# Sheet1.net
KiCad netlist of a schematic drawn in Altium Designer
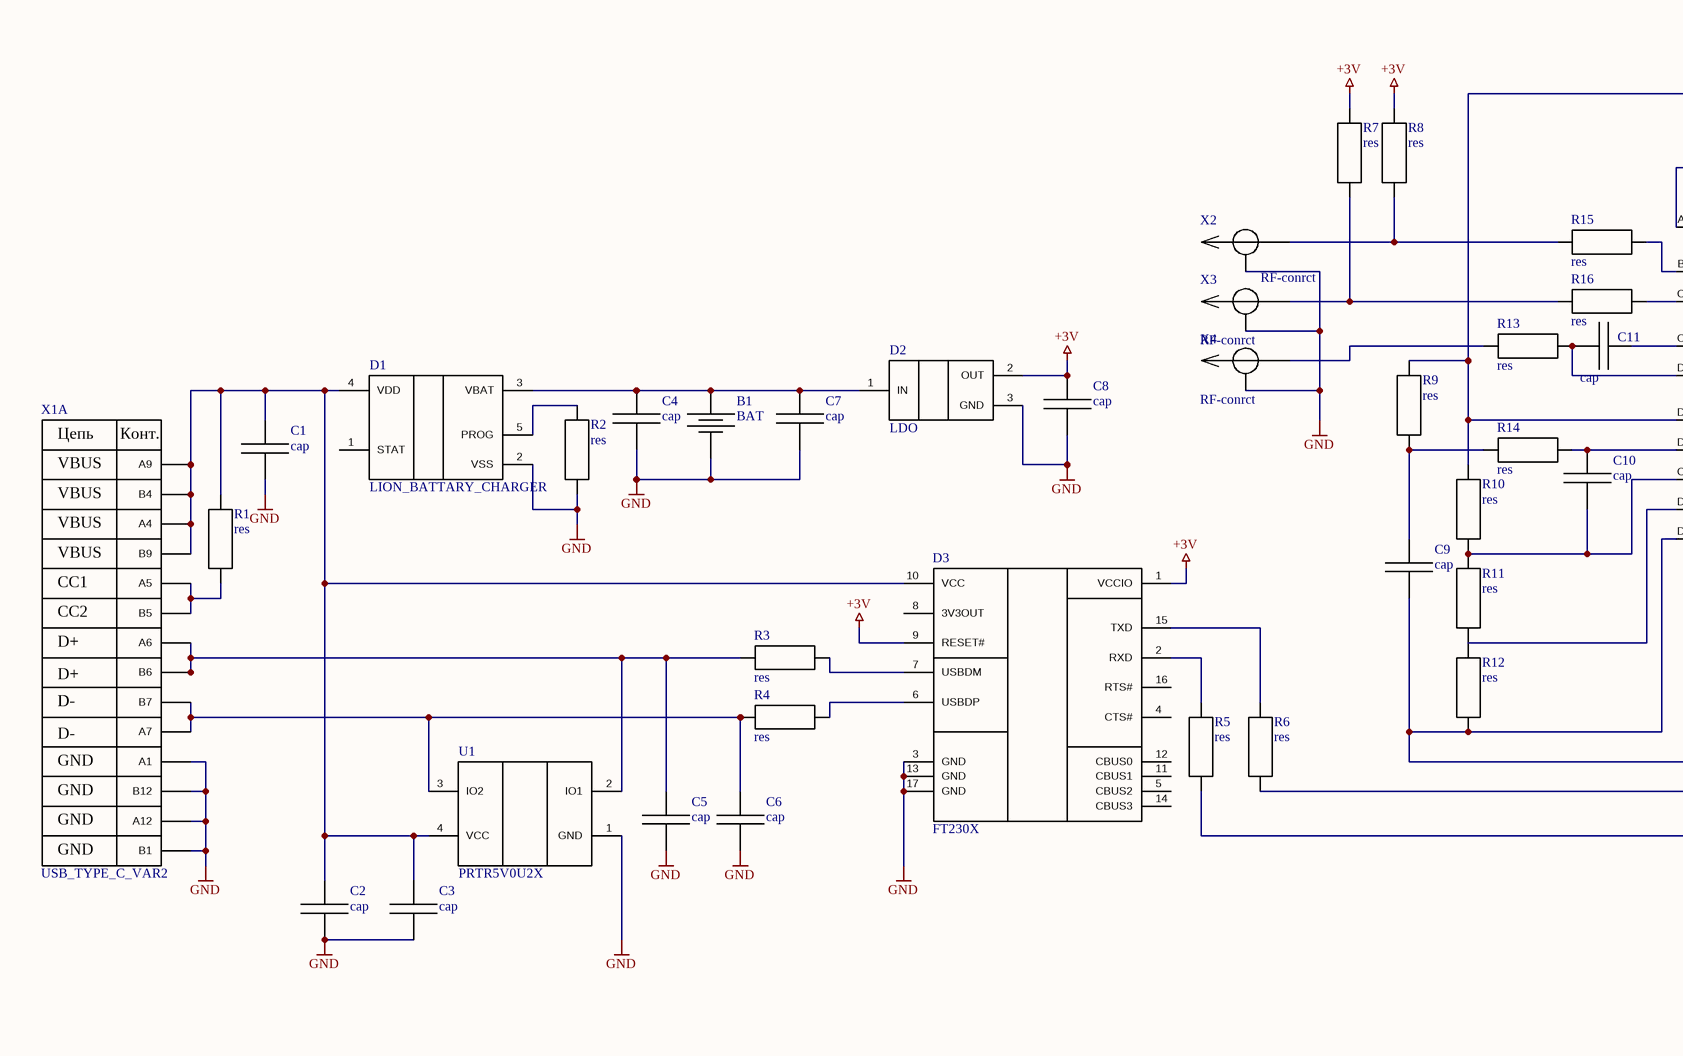
[diagram p0: Sheet1.SchDoc, left]
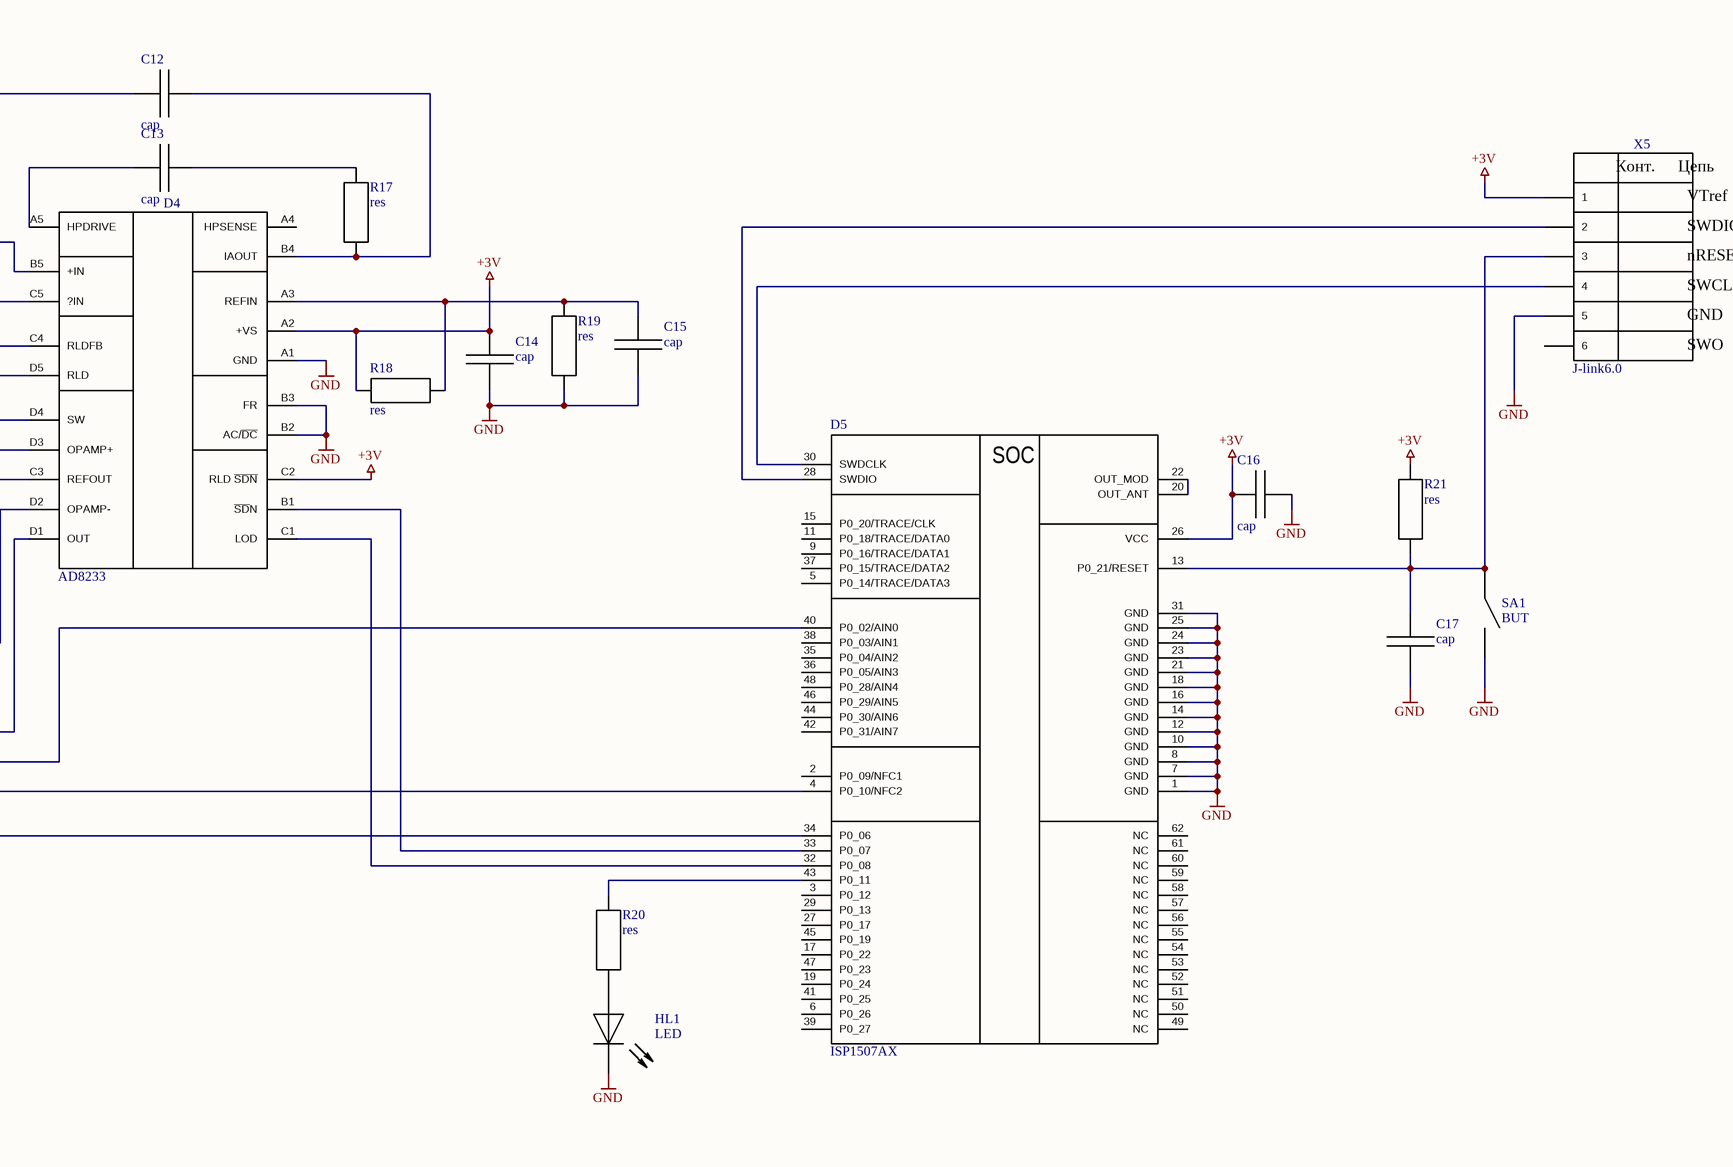
[diagram p1: Sheet1.SchDoc, right]

(export (version "E")
  (design (tool "Eeschema 10.0.6"))
  (components
    (comp (ref "B1")
      (value "BAT")
      (footprint "lION")
      (fields
        (field (name "PART NUMBER") "Li-Polymer 402025")
        (field (name "VOLTAGE") "3.7")
        (field (name "MANUFACTURER") "PKCELL")
      )
      (libsource (lib "lib_for_test_work") (part "BAT"))
    )
    (comp (ref "C1")
      (value "cap")
      (footprint "CAP0805")
      (fields
        (field (name "PART NUMBER") "GRM21BR71C475KA73L")
        (field (name "VOLTAGE") "16V")
        (field (name "MANUFACTURER") "Murata")
      )
      (libsource (lib "lib_for_test_work") (part "cap"))
    )
    (comp (ref "C2")
      (value "cap")
      (footprint "CAP0805")
      (fields
        (field (name "PART NUMBER") "GRM21BR71C475KA73L")
        (field (name "VOLTAGE") "16V")
        (field (name "MANUFACTURER") "Murata")
      )
      (libsource (lib "lib_for_test_work") (part "cap"))
    )
    (comp (ref "C3")
      (value "cap")
      (footprint "CAP0402")
      (fields
        (field (name "PART NUMBER") "GRM155R71C104K")
        (field (name "VOLTAGE") "10V")
        (field (name "MANUFACTURER") "Murata")
      )
      (libsource (lib "lib_for_test_work") (part "cap"))
    )
    (comp (ref "C4")
      (value "cap")
      (footprint "CAP0805")
      (fields
        (field (name "PART NUMBER") "GRM21BR71C475KA73L")
        (field (name "VOLTAGE") "16V")
        (field (name "MANUFACTURER") "Murata")
      )
      (libsource (lib "lib_for_test_work") (part "cap"))
    )
    (comp (ref "C5")
      (value "cap")
      (footprint "CAP0402")
      (fields
        (field (name "PART NUMBER") "GRM1555C1H470J")
        (field (name "VOLTAGE") "16V")
        (field (name "MANUFACTURER") "Murata")
      )
      (libsource (lib "lib_for_test_work") (part "cap"))
    )
    (comp (ref "C6")
      (value "cap")
      (footprint "CAP0402")
      (fields
        (field (name "PART NUMBER") "GRM1555C1H470J")
        (field (name "VOLTAGE") "16V")
        (field (name "MANUFACTURER") "Murata")
      )
      (libsource (lib "lib_for_test_work") (part "cap"))
    )
    (comp (ref "C7")
      (value "cap")
      (footprint "CAP0402")
      (fields
        (field (name "PART NUMBER") "GRM155R71C104K")
        (field (name "VOLTAGE") "10V")
        (field (name "MANUFACTURER") "Murata")
      )
      (libsource (lib "lib_for_test_work") (part "cap"))
    )
    (comp (ref "C8")
      (value "cap")
      (footprint "CAP0402")
      (fields
        (field (name "PART NUMBER") "GRM155R71C104K")
        (field (name "VOLTAGE") "10V")
        (field (name "MANUFACTURER") "Murata")
      )
      (libsource (lib "lib_for_test_work") (part "cap"))
    )
    (comp (ref "C9")
      (value "cap")
      (footprint "CAP0402")
      (fields
        (field (name "PART NUMBER") "GRM155R71H332KA01D")
        (field (name "VOLTAGE") "50V")
        (field (name "MANUFACTURER") "Murata")
      )
      (libsource (lib "lib_for_test_work") (part "cap"))
    )
    (comp (ref "C10")
      (value "cap")
      (footprint "CAP0402")
      (fields
        (field (name "PART NUMBER") "GRM155R71H223KA12B")
        (field (name "VOLTAGE") "50V")
        (field (name "MANUFACTURER") "Murata")
      )
      (libsource (lib "lib_for_test_work") (part "cap"))
    )
    (comp (ref "C11")
      (value "cap")
      (footprint "CAP0402")
      (fields
        (field (name "PART NUMBER") "GRM1555C1E102JA01D")
        (field (name "VOLTAGE") "16V")
        (field (name "MANUFACTURER") "Murata")
      )
      (libsource (lib "lib_for_test_work") (part "cap"))
    )
    (comp (ref "C12")
      (value "cap")
      (footprint "CAP0402")
      (fields
        (field (name "PART NUMBER") "GRM155R71C224KA12D")
        (field (name "VOLTAGE") "16V")
        (field (name "MANUFACTURER") "Murata")
      )
      (libsource (lib "lib_for_test_work") (part "cap"))
    )
    (comp (ref "C13")
      (value "cap")
      (footprint "CAP0402")
      (fields
        (field (name "PART NUMBER") "GRM155R71C224KA12D")
        (field (name "VOLTAGE") "16V")
        (field (name "MANUFACTURER") "Murata")
      )
      (libsource (lib "lib_for_test_work") (part "cap"))
    )
    (comp (ref "C14")
      (value "cap")
      (footprint "CAP0402")
      (fields
        (field (name "PART NUMBER") "GRM155R71C104K")
        (field (name "VOLTAGE") "10V")
        (field (name "MANUFACTURER") "Murata")
      )
      (libsource (lib "lib_for_test_work") (part "cap"))
    )
    (comp (ref "C15")
      (value "cap")
      (footprint "CAP0402")
      (fields
        (field (name "PART NUMBER") "GRM155R71C104K")
        (field (name "VOLTAGE") "10V")
        (field (name "MANUFACTURER") "Murata")
      )
      (libsource (lib "lib_for_test_work") (part "cap"))
    )
    (comp (ref "C16")
      (value "cap")
      (footprint "CAP0402")
      (fields
        (field (name "PART NUMBER") "GRM155R71C104K")
        (field (name "VOLTAGE") "10V")
        (field (name "MANUFACTURER") "Murata")
      )
      (libsource (lib "lib_for_test_work") (part "cap"))
    )
    (comp (ref "C17")
      (value "cap")
      (footprint "CAP0402")
      (fields
        (field (name "PART NUMBER") "GRM155R71C104K")
        (field (name "VOLTAGE") "10V")
        (field (name "MANUFACTURER") "Murata")
      )
      (libsource (lib "lib_for_test_work") (part "cap"))
    )
    (comp (ref "D1")
      (value "LION_BATTARY_CHARGER")
      (footprint "SOT95P270X15-5N")
      (fields (field (name "PART NUMBER") "MCP73831/2") (field (name "MANUFACTURER") "Microchip"))
      (libsource (lib "lib_for_test_work") (part "LION_BATTARY_CHARGER"))
    )
    (comp (ref "D2")
      (value "LDO")
      (footprint "SOT89-150P409X160-3N")
      (fields (field (name "PART NUMBER") "NJM78L03A") (field (name "MANUFACTURER") "JRC"))
      (libsource (lib "lib_for_test_work") (part "LDO"))
    )
    (comp (ref "D3")
      (value "FT230X")
      (footprint "PQFN65P400X400X80_HS-17N")
      (fields (field (name "MANUFACTURER") "FTDI Chip"))
      (libsource (lib "lib_for_test_work") (part "FT230X"))
    )
    (comp (ref "D4")
      (value "AD8233")
      (footprint "BGA20C40P5X4_204X171X56")
      (fields (field (name "MANUFACTURER") "Analog Devices"))
      (libsource (lib "lib_for_test_work") (part "AD8233"))
    )
    (comp (ref "D5")
      (value "ISP1507AX")
      (footprint "LGA6C330P2X3_800X800X100")
      (fields (field (name "PART NUMBER") "ISP1507") (field (name "MANUFACTURER") "Insight Sip"))
      (libsource (lib "lib_for_test_work") (part "ISP1507AX"))
    )
    (comp (ref "HL1")
      (value "LED")
      (footprint "Chip2PinSM127P600-8N")
      (fields (field (name "PART NUMBER") "KPHHS-1005CGCK") (field (name "MANUFACTURER") "Kingbring"))
      (libsource (lib "lib_for_test_work") (part "LED"))
    )
    (comp (ref "R1")
      (value "res")
      (footprint "RES0402")
      (fields
        (field (name "PART NUMBER") "RC0402FR-07100KL")
        (field (name "POWER") "0.062")
        (field (name "MANUFACTURER") "YAGEO")
      )
      (libsource (lib "lib_for_test_work") (part "res"))
    )
    (comp (ref "R2")
      (value "res")
      (footprint "RES0402")
      (fields
        (field (name "PART NUMBER") "RC0402FR-0713KL")
        (field (name "POWER") "0.062")
        (field (name "MANUFACTURER") "YAGEO")
      )
      (libsource (lib "lib_for_test_work") (part "res"))
    )
    (comp (ref "R3")
      (value "res")
      (footprint "RES0402")
      (fields
        (field (name "PART NUMBER") "RC0402FR-0727RL")
        (field (name "POWER") "0.062")
        (field (name "MANUFACTURER") "YAGEO")
      )
      (libsource (lib "lib_for_test_work") (part "res"))
    )
    (comp (ref "R4")
      (value "res")
      (footprint "RES0402")
      (fields
        (field (name "PART NUMBER") "RC0402FR-0727RL")
        (field (name "POWER") "0.062")
        (field (name "MANUFACTURER") "YAGEO")
      )
      (libsource (lib "lib_for_test_work") (part "res"))
    )
    (comp (ref "R5")
      (value "res")
      (footprint "RES0402")
      (fields
        (field (name "PART NUMBER") "RC0402JR-070RL")
        (field (name "POWER") "0.062")
        (field (name "MANUFACTURER") "YAGEO")
      )
      (libsource (lib "lib_for_test_work") (part "res"))
    )
    (comp (ref "R6")
      (value "res")
      (footprint "RES0402")
      (fields
        (field (name "PART NUMBER") "RC0402JR-070RL")
        (field (name "POWER") "0.062")
        (field (name "MANUFACTURER") "YAGEO")
      )
      (libsource (lib "lib_for_test_work") (part "res"))
    )
    (comp (ref "R7")
      (value "res")
      (footprint "RES0402")
      (fields
        (field (name "PART NUMBER") "RC0402FR-0710ML")
        (field (name "POWER") "0.062")
        (field (name "MANUFACTURER") "YAGEO")
      )
      (libsource (lib "lib_for_test_work") (part "res"))
    )
    (comp (ref "R8")
      (value "res")
      (footprint "RES0402")
      (fields
        (field (name "PART NUMBER") "RC0402FR-0710ML")
        (field (name "POWER") "0.062")
        (field (name "MANUFACTURER") "YAGEO")
      )
      (libsource (lib "lib_for_test_work") (part "res"))
    )
    (comp (ref "R9")
      (value "res")
      (footprint "RES0402")
      (fields
        (field (name "PART NUMBER") "RC0402FR-071ML")
        (field (name "POWER") "0.062")
        (field (name "MANUFACTURER") "YAGEO")
      )
      (libsource (lib "lib_for_test_work") (part "res"))
    )
    (comp (ref "R10")
      (value "res")
      (footprint "RES0402")
      (fields
        (field (name "PART NUMBER") "RC0402FR-07100KL")
        (field (name "POWER") "0.062")
        (field (name "MANUFACTURER") "YAGEO")
      )
      (libsource (lib "lib_for_test_work") (part "res"))
    )
    (comp (ref "R11")
      (value "res")
      (footprint "RES0402")
      (fields
        (field (name "PART NUMBER") "RC0402FR-07100KL")
        (field (name "POWER") "0.062")
        (field (name "MANUFACTURER") "YAGEO")
      )
      (libsource (lib "lib_for_test_work") (part "res"))
    )
    (comp (ref "R12")
      (value "res")
      (footprint "RES0402")
      (fields
        (field (name "PART NUMBER") "RC0402FR-071ML")
        (field (name "POWER") "0.062")
        (field (name "MANUFACTURER") "YAGEO")
      )
      (libsource (lib "lib_for_test_work") (part "res"))
    )
    (comp (ref "R13")
      (value "res")
      (footprint "RES0402")
      (fields
        (field (name "PART NUMBER") "RC0402FR-07360KL")
        (field (name "POWER") "0.062")
        (field (name "MANUFACTURER") "YAGEO")
      )
      (libsource (lib "lib_for_test_work") (part "res"))
    )
    (comp (ref "R14")
      (value "res")
      (footprint "RES0402")
      (fields
        (field (name "PART NUMBER") "RC0402FR-071ML")
        (field (name "POWER") "0.062")
        (field (name "MANUFACTURER") "YAGEO")
      )
      (libsource (lib "lib_for_test_work") (part "res"))
    )
    (comp (ref "R15")
      (value "res")
      (footprint "RES0402")
      (fields
        (field (name "PART NUMBER") "RC0402FR-07180KL")
        (field (name "POWER") "0.062")
        (field (name "MANUFACTURER") "YAGEO")
      )
      (libsource (lib "lib_for_test_work") (part "res"))
    )
    (comp (ref "R16")
      (value "res")
      (footprint "RES0402")
      (fields
        (field (name "PART NUMBER") "RC0402FR-07180KL")
        (field (name "POWER") "0.062")
        (field (name "MANUFACTURER") "YAGEO")
      )
      (libsource (lib "lib_for_test_work") (part "res"))
    )
    (comp (ref "R17")
      (value "res")
      (footprint "RES0402")
      (fields
        (field (name "PART NUMBER") "RC0402FR-0710ML")
        (field (name "POWER") "0.062")
        (field (name "MANUFACTURER") "YAGEO")
      )
      (libsource (lib "lib_for_test_work") (part "res"))
    )
    (comp (ref "R18")
      (value "res")
      (footprint "RES0402")
      (fields
        (field (name "PART NUMBER") "RC0402FR-0710ML")
        (field (name "POWER") "0.062")
        (field (name "MANUFACTURER") "YAGEO")
      )
      (libsource (lib "lib_for_test_work") (part "res"))
    )
    (comp (ref "R19")
      (value "res")
      (footprint "RES0402")
      (fields
        (field (name "PART NUMBER") "RC0402FR-0710ML")
        (field (name "POWER") "0.062")
        (field (name "MANUFACTURER") "YAGEO")
      )
      (libsource (lib "lib_for_test_work") (part "res"))
    )
    (comp (ref "R20")
      (value "res")
      (footprint "RES0402")
      (fields
        (field (name "PART NUMBER") "RC0402FR-0751RL")
        (field (name "POWER") "0.062")
        (field (name "MANUFACTURER") "YAGEO")
      )
      (libsource (lib "lib_for_test_work") (part "res"))
    )
    (comp (ref "R21")
      (value "res")
      (footprint "RES0402")
      (fields
        (field (name "PART NUMBER") "RC0402FR-0710KL")
        (field (name "POWER") "0.062")
        (field (name "MANUFACTURER") "YAGEO")
      )
      (libsource (lib "lib_for_test_work") (part "res"))
    )
    (comp (ref "SA1")
      (value "BUT")
      (footprint "IT-1184")
      (fields (field (name "PART NUMBER") "IT-1184") (field (name "MANUFACTURER") "Switronic"))
      (libsource (lib "lib_for_test_work") (part "BUT"))
    )
    (comp (ref "U1")
      (value "PRTR5V0U2X")
      (footprint "SOT143")
      (libsource (lib "lib_for_test_work") (part "PRTR5V0U2X"))
    )
    (comp (ref "X1")
      (value "USB_TYPE_C_VAR2")
      (footprint "WM12856CT-ND")
      (fields (field (name "PART NUMBER") "WM12856CT-ND") (field (name "MANUFACTURER") "Molex"))
      (libsource (lib "lib_for_test_work") (part "USB_TYPE_C_VAR2"))
    )
    (comp (ref "X2")
      (value "RF-conrct")
      (footprint "1909763-1")
      (fields (field (name "PART NUMBER") "1909763") (field (name "MANUFACTURER") "TE"))
      (libsource (lib "lib_for_test_work") (part "RF-conrct"))
    )
    (comp (ref "X3")
      (value "RF-conrct")
      (footprint "1909763-1")
      (fields (field (name "PART NUMBER") "1909763") (field (name "MANUFACTURER") "TE"))
      (libsource (lib "lib_for_test_work") (part "RF-conrct"))
    )
    (comp (ref "X4")
      (value "RF-conrct")
      (footprint "1909763-1")
      (fields (field (name "PART NUMBER") "1909763") (field (name "MANUFACTURER") "TE"))
      (libsource (lib "lib_for_test_work") (part "RF-conrct"))
    )
    (comp (ref "X5")
      (value "J-link6.0")
      (footprint "J-Link6.")
      (fields (field (name "PART NUMBER") "J-link6") (field (name "MANUFACTURER") "Jey Link"))
      (libsource (lib "lib_for_test_work") (part "J-link6.0"))
    )
  )
  (nets
    (net (code "1") (name "+3V") (class "Default")
      (node (ref "C14") (pin "1") (pinfunction "1_1") (pintype "passive"))
      (node (ref "C16") (pin "1") (pinfunction "1_1") (pintype "passive"))
      (node (ref "C8") (pin "1") (pinfunction "1_1") (pintype "passive"))
      (node (ref "D2") (pin "2") (pinfunction "OUT_2") (pintype "passive"))
      (node (ref "D3") (pin "1") (pinfunction "VCCIO_1") (pintype "passive"))
      (node (ref "D3") (pin "9") (pinfunction "RESET#_9") (pintype "passive"))
      (node (ref "D4") (pin "A2") (pinfunction "+VS_A2") (pintype "passive"))
      (node (ref "D4") (pin "C2") (pinfunction "RLD_~{SDN}_C2") (pintype "passive"))
      (node (ref "D5") (pin "26") (pinfunction "VCC_26") (pintype "passive"))
      (node (ref "R18") (pin "2") (pinfunction "2_2") (pintype "passive"))
      (node (ref "R21") (pin "1") (pinfunction "1_1") (pintype "passive"))
      (node (ref "R7") (pin "1") (pinfunction "1_1") (pintype "passive"))
      (node (ref "R8") (pin "1") (pinfunction "1_1") (pintype "passive"))
      (node (ref "X5") (pin "1") (pinfunction "1_1") (pintype "passive"))
    )
    (net (code "2") (name "GND") (class "Default")
      (node (ref "B1") (pin "2") (pinfunction "2_2") (pintype "passive"))
      (node (ref "C1") (pin "2") (pinfunction "2_2") (pintype "passive"))
      (node (ref "C14") (pin "2") (pinfunction "2_2") (pintype "passive"))
      (node (ref "C15") (pin "2") (pinfunction "2_2") (pintype "passive"))
      (node (ref "C16") (pin "2") (pinfunction "2_2") (pintype "passive"))
      (node (ref "C17") (pin "2") (pinfunction "2_2") (pintype "passive"))
      (node (ref "C2") (pin "2") (pinfunction "2_2") (pintype "passive"))
      (node (ref "C3") (pin "2") (pinfunction "2_2") (pintype "passive"))
      (node (ref "C4") (pin "2") (pinfunction "2_2") (pintype "passive"))
      (node (ref "C5") (pin "2") (pinfunction "2_2") (pintype "passive"))
      (node (ref "C6") (pin "2") (pinfunction "2_2") (pintype "passive"))
      (node (ref "C7") (pin "2") (pinfunction "2_2") (pintype "passive"))
      (node (ref "C8") (pin "2") (pinfunction "2_2") (pintype "passive"))
      (node (ref "D1") (pin "2") (pinfunction "VSS_2") (pintype "passive"))
      (node (ref "D2") (pin "3") (pinfunction "GND_3") (pintype "passive"))
      (node (ref "D3") (pin "13") (pinfunction "GND_13") (pintype "passive"))
      (node (ref "D3") (pin "17") (pinfunction "GND_17") (pintype "passive"))
      (node (ref "D3") (pin "3") (pinfunction "GND_3") (pintype "passive"))
      (node (ref "D4") (pin "A1") (pinfunction "GND_A1") (pintype "passive"))
      (node (ref "D4") (pin "B2") (pinfunction "AC/~{DC}_B2") (pintype "passive"))
      (node (ref "D4") (pin "B3") (pinfunction "FR_B3") (pintype "passive"))
      (node (ref "D5") (pin "1") (pinfunction "GND_1") (pintype "passive"))
      (node (ref "D5") (pin "10") (pinfunction "GND_10") (pintype "passive"))
      (node (ref "D5") (pin "12") (pinfunction "GND_12") (pintype "passive"))
      (node (ref "D5") (pin "14") (pinfunction "GND_14") (pintype "passive"))
      (node (ref "D5") (pin "16") (pinfunction "GND_16") (pintype "passive"))
      (node (ref "D5") (pin "18") (pinfunction "GND_18") (pintype "passive"))
      (node (ref "D5") (pin "21") (pinfunction "GND_21") (pintype "passive"))
      (node (ref "D5") (pin "23") (pinfunction "GND_23") (pintype "passive"))
      (node (ref "D5") (pin "24") (pinfunction "GND_24") (pintype "passive"))
      (node (ref "D5") (pin "25") (pinfunction "GND_25") (pintype "passive"))
      (node (ref "D5") (pin "31") (pinfunction "GND_31") (pintype "passive"))
      (node (ref "D5") (pin "7") (pinfunction "GND_7") (pintype "passive"))
      (node (ref "D5") (pin "8") (pinfunction "GND_8") (pintype "passive"))
      (node (ref "HL1") (pin "2") (pinfunction "K_2") (pintype "passive"))
      (node (ref "R19") (pin "1") (pinfunction "1_1") (pintype "passive"))
      (node (ref "R2") (pin "2") (pinfunction "2_2") (pintype "passive"))
      (node (ref "SA1") (pin "2") (pinfunction "2_2") (pintype "passive"))
      (node (ref "U1") (pin "1") (pinfunction "GND_1") (pintype "passive"))
      (node (ref "X1") (pin "A1") (pinfunction "A1_A1") (pintype "passive"))
      (node (ref "X1") (pin "A12") (pinfunction "A12_A12") (pintype "passive"))
      (node (ref "X1") (pin "B1") (pinfunction "B1_B1") (pintype "passive"))
      (node (ref "X1") (pin "B12") (pinfunction "B12_B12") (pintype "passive"))
      (node (ref "X2") (pin "2") (pinfunction "2_2") (pintype "passive"))
      (node (ref "X3") (pin "2") (pinfunction "2_2") (pintype "passive"))
      (node (ref "X4") (pin "2") (pinfunction "2_2") (pintype "passive"))
      (node (ref "X5") (pin "5") (pinfunction "5_5") (pintype "passive"))
    )
    (net (code "3") (name "Net-(C9-Pad1)") (class "Default")
      (node (ref "C9") (pin "1") (pinfunction "1_1") (pintype "passive"))
      (node (ref "R14") (pin "2") (pinfunction "2_2") (pintype "passive"))
      (node (ref "R9") (pin "1") (pinfunction "1_1") (pintype "passive"))
    )
    (net (code "4") (name "Net-(C13-Pad1)") (class "Default")
      (node (ref "C13") (pin "1") (pinfunction "1_1") (pintype "passive"))
      (node (ref "R17") (pin "1") (pinfunction "1_1") (pintype "passive"))
    )
    (net (code "5") (name "Net-(D1-PROG)") (class "Default")
      (node (ref "D1") (pin "5") (pinfunction "PROG_5") (pintype "passive"))
      (node (ref "R2") (pin "1") (pinfunction "1_1") (pintype "passive"))
    )
    (net (code "6") (name "Net-(D1-VBAT)") (class "Default")
      (node (ref "B1") (pin "1") (pinfunction "1_1") (pintype "passive"))
      (node (ref "C4") (pin "1") (pinfunction "1_1") (pintype "passive"))
      (node (ref "C7") (pin "1") (pinfunction "1_1") (pintype "passive"))
      (node (ref "D1") (pin "3") (pinfunction "VBAT_3") (pintype "passive"))
      (node (ref "D2") (pin "1") (pinfunction "IN_1") (pintype "passive"))
    )
    (net (code "7") (name "Net-(D1-VDD)") (class "Default")
      (node (ref "C1") (pin "1") (pinfunction "1_1") (pintype "passive"))
      (node (ref "C2") (pin "1") (pinfunction "1_1") (pintype "passive"))
      (node (ref "C3") (pin "1") (pinfunction "1_1") (pintype "passive"))
      (node (ref "D1") (pin "4") (pinfunction "VDD_4") (pintype "passive"))
      (node (ref "D3") (pin "10") (pinfunction "VCC_10") (pintype "passive"))
      (node (ref "R1") (pin "1") (pinfunction "1_1") (pintype "passive"))
      (node (ref "U1") (pin "4") (pinfunction "VCC_4") (pintype "passive"))
      (node (ref "X1") (pin "A4") (pinfunction "A4_A4") (pintype "passive"))
      (node (ref "X1") (pin "A9") (pinfunction "A9_A9") (pintype "passive"))
      (node (ref "X1") (pin "B4") (pinfunction "B4_B4") (pintype "passive"))
      (node (ref "X1") (pin "B9") (pinfunction "B9_B9") (pintype "passive"))
    )
    (net (code "8") (name "Net-(D3-RXD)") (class "Default")
      (node (ref "D3") (pin "2") (pinfunction "RXD_2") (pintype "passive"))
      (node (ref "R5") (pin "1") (pinfunction "1_1") (pintype "passive"))
    )
    (net (code "9") (name "Net-(D3-TXD)") (class "Default")
      (node (ref "D3") (pin "15") (pinfunction "TXD_15") (pintype "passive"))
      (node (ref "R6") (pin "1") (pinfunction "1_1") (pintype "passive"))
    )
    (net (code "10") (name "Net-(D3-USBDM)") (class "Default")
      (node (ref "D3") (pin "7") (pinfunction "USBDM_7") (pintype "passive"))
      (node (ref "R3") (pin "1") (pinfunction "1_1") (pintype "passive"))
    )
    (net (code "11") (name "Net-(D3-USBDP)") (class "Default")
      (node (ref "D3") (pin "6") (pinfunction "USBDP_6") (pintype "passive"))
      (node (ref "R4") (pin "1") (pinfunction "1_1") (pintype "passive"))
    )
    (net (code "12") (name "Net-(D4-+IN)") (class "Default")
      (node (ref "D4") (pin "B5") (pinfunction "+IN_B5") (pintype "passive"))
      (node (ref "R15") (pin "1") (pinfunction "1_1") (pintype "passive"))
    )
    (net (code "13") (name "Net-(D4-?IN)") (class "Default")
      (node (ref "D4") (pin "C5") (pinfunction "?IN_C5") (pintype "passive"))
      (node (ref "R16") (pin "1") (pinfunction "1_1") (pintype "passive"))
    )
    (net (code "14") (name "Net-(D4-HPDRIVE)") (class "Default")
      (node (ref "C13") (pin "2") (pinfunction "2_2") (pintype "passive"))
      (node (ref "D4") (pin "A5") (pinfunction "HPDRIVE_A5") (pintype "passive"))
    )
    (net (code "15") (name "Net-(D4-IAOUT)") (class "Default")
      (node (ref "C12") (pin "1") (pinfunction "1_1") (pintype "passive"))
      (node (ref "D4") (pin "B4") (pinfunction "IAOUT_B4") (pintype "passive"))
      (node (ref "R17") (pin "2") (pinfunction "2_2") (pintype "passive"))
    )
    (net (code "16") (name "Net-(D4-LOD)") (class "Default")
      (node (ref "D4") (pin "C1") (pinfunction "LOD_C1") (pintype "passive"))
      (node (ref "D5") (pin "32") (pinfunction "P0_08_32") (pintype "passive"))
    )
    (net (code "17") (name "Net-(D4-OPAMP+)") (class "Default")
      (node (ref "C10") (pin "1") (pinfunction "1_1") (pintype "passive"))
      (node (ref "D4") (pin "D3") (pinfunction "OPAMP+_D3") (pintype "passive"))
      (node (ref "R14") (pin "1") (pinfunction "1_1") (pintype "passive"))
    )
    (net (code "18") (name "Net-(D4-OPAMP-)") (class "Default")
      (node (ref "D4") (pin "D2") (pinfunction "OPAMP-_D2") (pintype "passive"))
      (node (ref "R11") (pin "2") (pinfunction "2_2") (pintype "passive"))
      (node (ref "R12") (pin "2") (pinfunction "2_2") (pintype "passive"))
    )
    (net (code "19") (name "Net-(D4-OUT)") (class "Default")
      (node (ref "C9") (pin "2") (pinfunction "2_2") (pintype "passive"))
      (node (ref "D4") (pin "D1") (pinfunction "OUT_D1") (pintype "passive"))
      (node (ref "D5") (pin "40") (pinfunction "P0_02/AIN0_40") (pintype "passive"))
      (node (ref "R12") (pin "1") (pinfunction "1_1") (pintype "passive"))
    )
    (net (code "20") (name "Net-(D4-REFIN)") (class "Default")
      (node (ref "C15") (pin "1") (pinfunction "1_1") (pintype "passive"))
      (node (ref "D4") (pin "A3") (pinfunction "REFIN_A3") (pintype "passive"))
      (node (ref "R18") (pin "1") (pinfunction "1_1") (pintype "passive"))
      (node (ref "R19") (pin "2") (pinfunction "2_2") (pintype "passive"))
    )
    (net (code "21") (name "Net-(D4-REFOUT)") (class "Default")
      (node (ref "C10") (pin "2") (pinfunction "2_2") (pintype "passive"))
      (node (ref "D4") (pin "C3") (pinfunction "REFOUT_C3") (pintype "passive"))
      (node (ref "R10") (pin "2") (pinfunction "2_2") (pintype "passive"))
      (node (ref "R11") (pin "1") (pinfunction "1_1") (pintype "passive"))
    )
    (net (code "22") (name "Net-(D4-RLD)") (class "Default")
      (node (ref "C11") (pin "2") (pinfunction "2_2") (pintype "passive"))
      (node (ref "D4") (pin "D5") (pinfunction "RLD_D5") (pintype "passive"))
      (node (ref "R13") (pin "1") (pinfunction "1_1") (pintype "passive"))
    )
    (net (code "23") (name "Net-(D4-RLDFB)") (class "Default")
      (node (ref "C11") (pin "1") (pinfunction "1_1") (pintype "passive"))
      (node (ref "D4") (pin "C4") (pinfunction "RLDFB_C4") (pintype "passive"))
    )
    (net (code "24") (name "Net-(D4-SW)") (class "Default")
      (node (ref "C12") (pin "2") (pinfunction "2_2") (pintype "passive"))
      (node (ref "D4") (pin "D4") (pinfunction "SW_D4") (pintype "passive"))
      (node (ref "R10") (pin "1") (pinfunction "1_1") (pintype "passive"))
      (node (ref "R9") (pin "2") (pinfunction "2_2") (pintype "passive"))
    )
    (net (code "25") (name "Net-(D4-~{SD}N)") (class "Default")
      (node (ref "D4") (pin "B1") (pinfunction "~{SD}N_B1") (pintype "passive"))
      (node (ref "D5") (pin "33") (pinfunction "P0_07_33") (pintype "passive"))
    )
    (net (code "26") (name "Net-(D5-OUT_ANT)") (class "Default")
      (node (ref "D5") (pin "20") (pinfunction "OUT_ANT_20") (pintype "passive"))
      (node (ref "D5") (pin "22") (pinfunction "OUT_MOD_22") (pintype "passive"))
    )
    (net (code "27") (name "Net-(D5-P0_06)") (class "Default")
      (node (ref "D5") (pin "34") (pinfunction "P0_06_34") (pintype "passive"))
      (node (ref "R5") (pin "2") (pinfunction "2_2") (pintype "passive"))
    )
    (net (code "28") (name "Net-(D5-P0_10{slash}NFC2)") (class "Default")
      (node (ref "D5") (pin "4") (pinfunction "P0_10/NFC2_4") (pintype "passive"))
      (node (ref "R6") (pin "2") (pinfunction "2_2") (pintype "passive"))
    )
    (net (code "29") (name "Net-(D5-P0_11)") (class "Default")
      (node (ref "D5") (pin "43") (pinfunction "P0_11_43") (pintype "passive"))
      (node (ref "R20") (pin "1") (pinfunction "1_1") (pintype "passive"))
    )
    (net (code "30") (name "Net-(D5-P0_21{slash}RESET)") (class "Default")
      (node (ref "C17") (pin "1") (pinfunction "1_1") (pintype "passive"))
      (node (ref "D5") (pin "13") (pinfunction "P0_21/RESET_13") (pintype "passive"))
      (node (ref "R21") (pin "2") (pinfunction "2_2") (pintype "passive"))
      (node (ref "SA1") (pin "1") (pinfunction "1_1") (pintype "passive"))
      (node (ref "X5") (pin "3") (pinfunction "3_3") (pintype "passive"))
    )
    (net (code "31") (name "Net-(D5-SWDCLK)") (class "Default")
      (node (ref "D5") (pin "30") (pinfunction "SWDCLK_30") (pintype "passive"))
      (node (ref "X5") (pin "4") (pinfunction "4_4") (pintype "passive"))
    )
    (net (code "32") (name "Net-(D5-SWDIO)") (class "Default")
      (node (ref "D5") (pin "28") (pinfunction "SWDIO_28") (pintype "passive"))
      (node (ref "X5") (pin "2") (pinfunction "2_2") (pintype "passive"))
    )
    (net (code "33") (name "Net-(HL1-A)") (class "Default")
      (node (ref "HL1") (pin "1") (pinfunction "A_1") (pintype "passive"))
      (node (ref "R20") (pin "2") (pinfunction "2_2") (pintype "passive"))
    )
    (net (code "34") (name "Net-(R1-Pad2)") (class "Default")
      (node (ref "R1") (pin "2") (pinfunction "2_2") (pintype "passive"))
      (node (ref "X1") (pin "A5") (pinfunction "A5_A5") (pintype "passive"))
      (node (ref "X1") (pin "B5") (pinfunction "B5_B5") (pintype "passive"))
    )
    (net (code "35") (name "Net-(R13-Pad2)") (class "Default")
      (node (ref "R13") (pin "2") (pinfunction "2_2") (pintype "passive"))
      (node (ref "X4") (pin "1") (pinfunction "1_1") (pintype "passive"))
    )
    (net (code "36") (name "Net-(R15-Pad2)") (class "Default")
      (node (ref "R15") (pin "2") (pinfunction "2_2") (pintype "passive"))
      (node (ref "R8") (pin "2") (pinfunction "2_2") (pintype "passive"))
      (node (ref "X2") (pin "1") (pinfunction "1_1") (pintype "passive"))
    )
    (net (code "37") (name "Net-(R16-Pad2)") (class "Default")
      (node (ref "R16") (pin "2") (pinfunction "2_2") (pintype "passive"))
      (node (ref "R7") (pin "2") (pinfunction "2_2") (pintype "passive"))
      (node (ref "X3") (pin "1") (pinfunction "1_1") (pintype "passive"))
    )
    (net (code "38") (name "Net-(U1-IO1)") (class "Default")
      (node (ref "C5") (pin "1") (pinfunction "1_1") (pintype "passive"))
      (node (ref "R3") (pin "2") (pinfunction "2_2") (pintype "passive"))
      (node (ref "U1") (pin "2") (pinfunction "IO1_2") (pintype "passive"))
      (node (ref "X1") (pin "A6") (pinfunction "A6_A6") (pintype "passive"))
      (node (ref "X1") (pin "B6") (pinfunction "B6_B6") (pintype "passive"))
    )
    (net (code "39") (name "Net-(U1-IO2)") (class "Default")
      (node (ref "C6") (pin "1") (pinfunction "1_1") (pintype "passive"))
      (node (ref "R4") (pin "2") (pinfunction "2_2") (pintype "passive"))
      (node (ref "U1") (pin "3") (pinfunction "IO2_3") (pintype "passive"))
      (node (ref "X1") (pin "A7") (pinfunction "A7_A7") (pintype "passive"))
      (node (ref "X1") (pin "B7") (pinfunction "B7_B7") (pintype "passive"))
    )
    (net (code "40") (name "unconnected-(D1-STAT-Pad1)") (class "Default")
      (node (ref "D1") (pin "1") (pinfunction "STAT_1") (pintype "passive"))
    )
    (net (code "41") (name "unconnected-(D3-3V3OUT-Pad8)") (class "Default")
      (node (ref "D3") (pin "8") (pinfunction "3V3OUT_8") (pintype "passive"))
    )
    (net (code "42") (name "unconnected-(D3-CBUS0-Pad12)") (class "Default")
      (node (ref "D3") (pin "12") (pinfunction "CBUS0_12") (pintype "passive"))
    )
    (net (code "43") (name "unconnected-(D3-CBUS1-Pad11)") (class "Default")
      (node (ref "D3") (pin "11") (pinfunction "CBUS1_11") (pintype "passive"))
    )
    (net (code "44") (name "unconnected-(D3-CBUS2-Pad5)") (class "Default")
      (node (ref "D3") (pin "5") (pinfunction "CBUS2_5") (pintype "passive"))
    )
    (net (code "45") (name "unconnected-(D3-CBUS3-Pad14)") (class "Default")
      (node (ref "D3") (pin "14") (pinfunction "CBUS3_14") (pintype "passive"))
    )
    (net (code "46") (name "unconnected-(D3-CTS#-Pad4)") (class "Default")
      (node (ref "D3") (pin "4") (pinfunction "CTS#_4") (pintype "passive"))
    )
    (net (code "47") (name "unconnected-(D3-RTS#-Pad16)") (class "Default")
      (node (ref "D3") (pin "16") (pinfunction "RTS#_16") (pintype "passive"))
    )
    (net (code "48") (name "unconnected-(D4-HPSENSE-PadA4)") (class "Default")
      (node (ref "D4") (pin "A4") (pinfunction "HPSENSE_A4") (pintype "passive"))
    )
    (net (code "49") (name "unconnected-(D5-NC-Pad49)") (class "Default")
      (node (ref "D5") (pin "49") (pinfunction "NC_49") (pintype "passive"))
    )
    (net (code "50") (name "unconnected-(D5-NC-Pad50)") (class "Default")
      (node (ref "D5") (pin "50") (pinfunction "NC_50") (pintype "passive"))
    )
    (net (code "51") (name "unconnected-(D5-NC-Pad51)") (class "Default")
      (node (ref "D5") (pin "51") (pinfunction "NC_51") (pintype "passive"))
    )
    (net (code "52") (name "unconnected-(D5-NC-Pad52)") (class "Default")
      (node (ref "D5") (pin "52") (pinfunction "NC_52") (pintype "passive"))
    )
    (net (code "53") (name "unconnected-(D5-NC-Pad53)") (class "Default")
      (node (ref "D5") (pin "53") (pinfunction "NC_53") (pintype "passive"))
    )
    (net (code "54") (name "unconnected-(D5-NC-Pad54)") (class "Default")
      (node (ref "D5") (pin "54") (pinfunction "NC_54") (pintype "passive"))
    )
    (net (code "55") (name "unconnected-(D5-NC-Pad55)") (class "Default")
      (node (ref "D5") (pin "55") (pinfunction "NC_55") (pintype "passive"))
    )
    (net (code "56") (name "unconnected-(D5-NC-Pad56)") (class "Default")
      (node (ref "D5") (pin "56") (pinfunction "NC_56") (pintype "passive"))
    )
    (net (code "57") (name "unconnected-(D5-NC-Pad57)") (class "Default")
      (node (ref "D5") (pin "57") (pinfunction "NC_57") (pintype "passive"))
    )
    (net (code "58") (name "unconnected-(D5-NC-Pad58)") (class "Default")
      (node (ref "D5") (pin "58") (pinfunction "NC_58") (pintype "passive"))
    )
    (net (code "59") (name "unconnected-(D5-NC-Pad59)") (class "Default")
      (node (ref "D5") (pin "59") (pinfunction "NC_59") (pintype "passive"))
    )
    (net (code "60") (name "unconnected-(D5-NC-Pad60)") (class "Default")
      (node (ref "D5") (pin "60") (pinfunction "NC_60") (pintype "passive"))
    )
    (net (code "61") (name "unconnected-(D5-NC-Pad61)") (class "Default")
      (node (ref "D5") (pin "61") (pinfunction "NC_61") (pintype "passive"))
    )
    (net (code "62") (name "unconnected-(D5-NC-Pad62)") (class "Default")
      (node (ref "D5") (pin "62") (pinfunction "NC_62") (pintype "passive"))
    )
    (net (code "63") (name "unconnected-(D5-P0_03{slash}AIN1-Pad38)") (class "Default")
      (node (ref "D5") (pin "38") (pinfunction "P0_03/AIN1_38") (pintype "passive"))
    )
    (net (code "64") (name "unconnected-(D5-P0_04{slash}AIN2-Pad35)") (class "Default")
      (node (ref "D5") (pin "35") (pinfunction "P0_04/AIN2_35") (pintype "passive"))
    )
    (net (code "65") (name "unconnected-(D5-P0_05{slash}AIN3-Pad36)") (class "Default")
      (node (ref "D5") (pin "36") (pinfunction "P0_05/AIN3_36") (pintype "passive"))
    )
    (net (code "66") (name "unconnected-(D5-P0_09{slash}NFC1-Pad2)") (class "Default")
      (node (ref "D5") (pin "2") (pinfunction "P0_09/NFC1_2") (pintype "passive"))
    )
    (net (code "67") (name "unconnected-(D5-P0_12-Pad3)") (class "Default")
      (node (ref "D5") (pin "3") (pinfunction "P0_12_3") (pintype "passive"))
    )
    (net (code "68") (name "unconnected-(D5-P0_13-Pad29)") (class "Default")
      (node (ref "D5") (pin "29") (pinfunction "P0_13_29") (pintype "passive"))
    )
    (net (code "69") (name "unconnected-(D5-P0_14{slash}TRACE{slash}DATA3-Pad5)") (class "Default")
      (node (ref "D5") (pin "5") (pinfunction "P0_14/TRACE/DATA3_5") (pintype "passive"))
    )
    (net (code "70") (name "unconnected-(D5-P0_15{slash}TRACE{slash}DATA2-Pad37)") (class "Default")
      (node (ref "D5") (pin "37") (pinfunction "P0_15/TRACE/DATA2_37") (pintype "passive"))
    )
    (net (code "71") (name "unconnected-(D5-P0_16{slash}TRACE{slash}DATA1-Pad9)") (class "Default")
      (node (ref "D5") (pin "9") (pinfunction "P0_16/TRACE/DATA1_9") (pintype "passive"))
    )
    (net (code "72") (name "unconnected-(D5-P0_17-Pad27)") (class "Default")
      (node (ref "D5") (pin "27") (pinfunction "P0_17_27") (pintype "passive"))
    )
    (net (code "73") (name "unconnected-(D5-P0_18{slash}TRACE{slash}DATA0-Pad11)") (class "Default")
      (node (ref "D5") (pin "11") (pinfunction "P0_18/TRACE/DATA0_11") (pintype "passive"))
    )
    (net (code "74") (name "unconnected-(D5-P0_19-Pad45)") (class "Default")
      (node (ref "D5") (pin "45") (pinfunction "P0_19_45") (pintype "passive"))
    )
    (net (code "75") (name "unconnected-(D5-P0_20{slash}TRACE{slash}CLK-Pad15)") (class "Default")
      (node (ref "D5") (pin "15") (pinfunction "P0_20/TRACE/CLK_15") (pintype "passive"))
    )
    (net (code "76") (name "unconnected-(D5-P0_22-Pad17)") (class "Default")
      (node (ref "D5") (pin "17") (pinfunction "P0_22_17") (pintype "passive"))
    )
    (net (code "77") (name "unconnected-(D5-P0_23-Pad47)") (class "Default")
      (node (ref "D5") (pin "47") (pinfunction "P0_23_47") (pintype "passive"))
    )
    (net (code "78") (name "unconnected-(D5-P0_24-Pad19)") (class "Default")
      (node (ref "D5") (pin "19") (pinfunction "P0_24_19") (pintype "passive"))
    )
    (net (code "79") (name "unconnected-(D5-P0_25-Pad41)") (class "Default")
      (node (ref "D5") (pin "41") (pinfunction "P0_25_41") (pintype "passive"))
    )
    (net (code "80") (name "unconnected-(D5-P0_26-Pad6)") (class "Default")
      (node (ref "D5") (pin "6") (pinfunction "P0_26_6") (pintype "passive"))
    )
    (net (code "81") (name "unconnected-(D5-P0_27-Pad39)") (class "Default")
      (node (ref "D5") (pin "39") (pinfunction "P0_27_39") (pintype "passive"))
    )
    (net (code "82") (name "unconnected-(D5-P0_28{slash}AIN4-Pad48)") (class "Default")
      (node (ref "D5") (pin "48") (pinfunction "P0_28/AIN4_48") (pintype "passive"))
    )
    (net (code "83") (name "unconnected-(D5-P0_29{slash}AIN5-Pad46)") (class "Default")
      (node (ref "D5") (pin "46") (pinfunction "P0_29/AIN5_46") (pintype "passive"))
    )
    (net (code "84") (name "unconnected-(D5-P0_30{slash}AIN6-Pad44)") (class "Default")
      (node (ref "D5") (pin "44") (pinfunction "P0_30/AIN6_44") (pintype "passive"))
    )
    (net (code "85") (name "unconnected-(D5-P0_31{slash}AIN7-Pad42)") (class "Default")
      (node (ref "D5") (pin "42") (pinfunction "P0_31/AIN7_42") (pintype "passive"))
    )
    (net (code "86") (name "unconnected-(X5-Pad6)") (class "Default")
      (node (ref "X5") (pin "6") (pinfunction "6_6") (pintype "passive"))
    )
  )
)
